# ARM_CTR_STM_DRV.net
KiCad netlist of a schematic drawn in Altium Designer
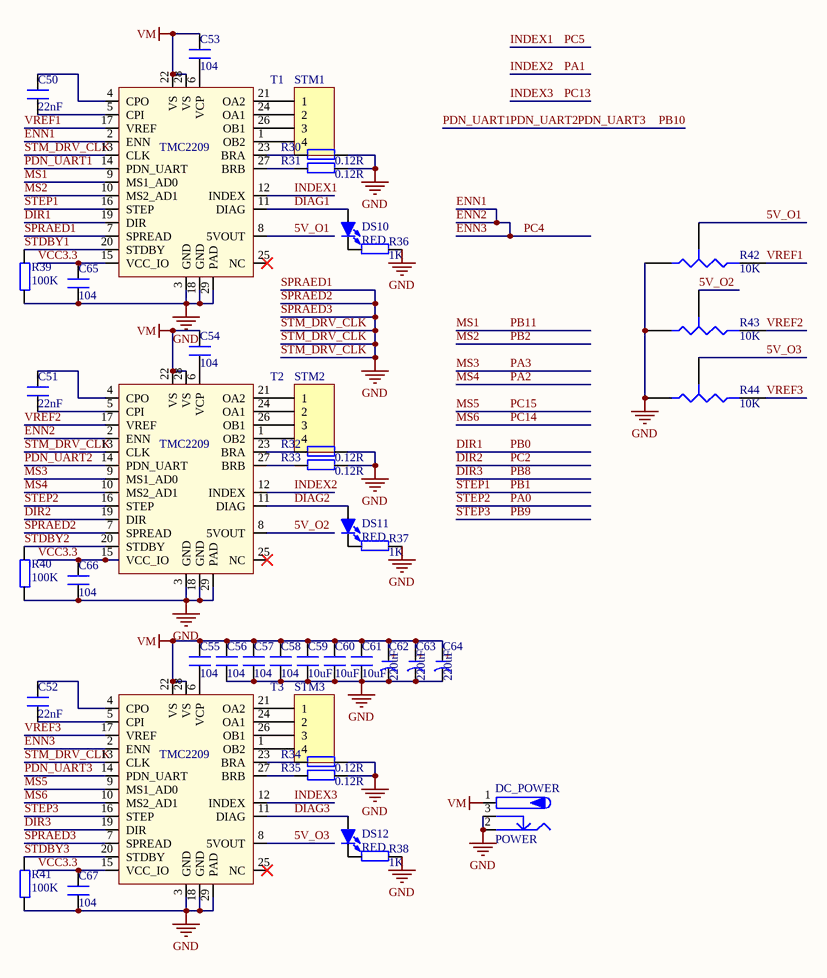
[diagram p0: ARM_CTR_STM_DRV.SchDoc]

(export (version "E")
  (design (tool "Eeschema 10.0.6"))
  (components
    (comp (ref "C50")
      (value "22nF")
      (footprint "C 0603_L")
      (libsource (lib "WarShip V3 STM32103封装库") (part "C"))
    )
    (comp (ref "C51")
      (value "22nF")
      (footprint "C 0603_L")
      (libsource (lib "WarShip V3 STM32103封装库") (part "C"))
    )
    (comp (ref "C52")
      (value "22nF")
      (footprint "C 0603_L")
      (libsource (lib "WarShip V3 STM32103封装库") (part "C"))
    )
    (comp (ref "C53")
      (value "104")
      (footprint "C 0603_L")
      (libsource (lib "WarShip V3 STM32103封装库") (part "C"))
    )
    (comp (ref "C54")
      (value "104")
      (footprint "C 0603_L")
      (libsource (lib "WarShip V3 STM32103封装库") (part "C"))
    )
    (comp (ref "C55")
      (value "104")
      (footprint "C 0603_L")
      (libsource (lib "WarShip V3 STM32103封装库") (part "C"))
    )
    (comp (ref "C56")
      (value "104")
      (footprint "C 0603_L")
      (libsource (lib "WarShip V3 STM32103封装库") (part "C"))
    )
    (comp (ref "C57")
      (value "104")
      (footprint "C 0603_L")
      (libsource (lib "WarShip V3 STM32103封装库") (part "C"))
    )
    (comp (ref "C58")
      (value "104")
      (footprint "C 0603_L")
      (libsource (lib "WarShip V3 STM32103封装库") (part "C"))
    )
    (comp (ref "C59")
      (value "10uF")
      (footprint "C 0603_L")
      (libsource (lib "WarShip V3 STM32103封装库") (part "C"))
    )
    (comp (ref "C60")
      (value "10uF")
      (footprint "C 0603_L")
      (libsource (lib "WarShip V3 STM32103封装库") (part "C"))
    )
    (comp (ref "C61")
      (value "10uF")
      (footprint "C 0603_L")
      (libsource (lib "WarShip V3 STM32103封装库") (part "C"))
    )
    (comp (ref "C62")
      (value "220uF")
      (footprint "CM D(6.3*5.4)")
      (description "贴片电解电容")
      (fields (field (name "版权归属") "源创客"))
      (libsource (lib "IMX6UL_ALPHA(底板)_V2.0") (part "C-CM"))
    )
    (comp (ref "C63")
      (value "220uF")
      (footprint "CM D(6.3*5.4)")
      (description "贴片电解电容")
      (fields (field (name "版权归属") "源创客"))
      (libsource (lib "IMX6UL_ALPHA(底板)_V2.0") (part "C-CM"))
    )
    (comp (ref "C64")
      (value "220uF")
      (footprint "CM D(6.3*5.4)")
      (description "贴片电解电容")
      (fields (field (name "版权归属") "源创客"))
      (libsource (lib "IMX6UL_ALPHA(底板)_V2.0") (part "C-CM"))
    )
    (comp (ref "C65")
      (value "104")
      (footprint "C 0603_L")
      (libsource (lib "WarShip V3 STM32103封装库") (part "C"))
    )
    (comp (ref "C66")
      (value "104")
      (footprint "C 0603_L")
      (libsource (lib "WarShip V3 STM32103封装库") (part "C"))
    )
    (comp (ref "C67")
      (value "104")
      (footprint "C 0603_L")
      (libsource (lib "WarShip V3 STM32103封装库") (part "C"))
    )
    (comp (ref "DC_POWER")
      (value "POWER")
      (footprint "DC10B")
      (description "低压电源接口")
      (fields (field (name "版权归属") "源创客"))
      (libsource (lib "IMX6UL_ALPHA(底板)_V2.0") (part "P-DC"))
    )
    (comp (ref "DS10")
      (value "RED")
      (footprint "LED 0805R")
      (description "贴片LED")
      (fields (field (name "版权归属") "源创客"))
      (libsource (lib "IMX6UL_ALPHA(底板)_V2.0") (part "LED-SMD"))
    )
    (comp (ref "DS11")
      (value "RED")
      (footprint "LED 0805R")
      (description "贴片LED")
      (fields (field (name "版权归属") "源创客"))
      (libsource (lib "IMX6UL_ALPHA(底板)_V2.0") (part "LED-SMD"))
    )
    (comp (ref "DS12")
      (value "RED")
      (footprint "LED 0805R")
      (description "贴片LED")
      (fields (field (name "版权归属") "源创客"))
      (libsource (lib "IMX6UL_ALPHA(底板)_V2.0") (part "LED-SMD"))
    )
    (comp (ref "R30")
      (value "0.12R")
      (footprint "R 0805_L")
      (libsource (lib "WarShip V3 STM32103封装库") (part "R"))
    )
    (comp (ref "R31")
      (value "0.12R")
      (footprint "R 0805_L")
      (libsource (lib "WarShip V3 STM32103封装库") (part "R"))
    )
    (comp (ref "R32")
      (value "0.12R")
      (footprint "R 0805_L")
      (libsource (lib "WarShip V3 STM32103封装库") (part "R"))
    )
    (comp (ref "R33")
      (value "0.12R")
      (footprint "R 0805_L")
      (libsource (lib "WarShip V3 STM32103封装库") (part "R"))
    )
    (comp (ref "R34")
      (value "0.12R")
      (footprint "R 0805_L")
      (libsource (lib "WarShip V3 STM32103封装库") (part "R"))
    )
    (comp (ref "R35")
      (value "0.12R")
      (footprint "R 0805_L")
      (libsource (lib "WarShip V3 STM32103封装库") (part "R"))
    )
    (comp (ref "R36")
      (value "1K")
      (footprint "R 0603_L")
      (libsource (lib "WarShip V3 STM32103封装库") (part "R"))
    )
    (comp (ref "R37")
      (value "1K")
      (footprint "R 0603_L")
      (libsource (lib "WarShip V3 STM32103封装库") (part "R"))
    )
    (comp (ref "R38")
      (value "1K")
      (footprint "R 0603_L")
      (libsource (lib "WarShip V3 STM32103封装库") (part "R"))
    )
    (comp (ref "R39")
      (value "100K")
      (footprint "R 0603_L")
      (libsource (lib "WarShip V3 STM32103封装库") (part "R"))
    )
    (comp (ref "R40")
      (value "100K")
      (footprint "R 0603_L")
      (libsource (lib "WarShip V3 STM32103封装库") (part "R"))
    )
    (comp (ref "R41")
      (value "100K")
      (footprint "R 0603_L")
      (libsource (lib "WarShip V3 STM32103封装库") (part "R"))
    )
    (comp (ref "R42")
      (value "10K")
      (footprint "3362P")
      (description "Tapped Resistor")
      (fields (field (name "Comment") "Res Tap") (field (name "PUBLISHER") "Altium Limited"))
      (libsource (lib "Miscellaneous Devices") (part "Res Tap"))
    )
    (comp (ref "R43")
      (value "10K")
      (footprint "3362P")
      (description "Tapped Resistor")
      (fields (field (name "Comment") "Res Tap") (field (name "PUBLISHER") "Altium Limited"))
      (libsource (lib "Miscellaneous Devices") (part "Res Tap"))
    )
    (comp (ref "R44")
      (value "10K")
      (footprint "3362P")
      (description "Tapped Resistor")
      (fields (field (name "Comment") "Res Tap") (field (name "PUBLISHER") "Altium Limited"))
      (libsource (lib "Miscellaneous Devices") (part "Res Tap"))
    )
    (comp (ref "STM1")
      (value "Header 4")
      (footprint "XH2.54-WI-4P")
      (description "Header, 4-Pin")
      (fields (field (name "PUBLISHER") "Altium Limited"))
      (libsource (lib "Miscellaneous Connectors") (part "Header 4"))
    )
    (comp (ref "STM2")
      (value "Header 4")
      (footprint "XH2.54-WI-4P")
      (description "Header, 4-Pin")
      (fields (field (name "PUBLISHER") "Altium Limited"))
      (libsource (lib "Miscellaneous Connectors") (part "Header 4"))
    )
    (comp (ref "STM3")
      (value "Header 4")
      (footprint "XH2.54-WI-4P")
      (description "Header, 4-Pin")
      (fields (field (name "PUBLISHER") "Altium Limited"))
      (libsource (lib "Miscellaneous Connectors") (part "Header 4"))
    )
    (comp (ref "T1")
      (value "TMC2209")
      (footprint "QFN28 5x5_L")
      (description "步进电机驱动芯片")
      (libsource (lib "MINIBLDC") (part "TMC2209"))
    )
    (comp (ref "T2")
      (value "TMC2209")
      (footprint "QFN28 5x5_L")
      (description "步进电机驱动芯片")
      (libsource (lib "MINIBLDC") (part "TMC2209"))
    )
    (comp (ref "T3")
      (value "TMC2209")
      (footprint "QFN28 5x5_L")
      (description "步进电机驱动芯片")
      (libsource (lib "MINIBLDC") (part "TMC2209"))
    )
  )
  (nets
    (net (code "1") (name "/5V_O1") (class "Default")
      (node (ref "R42") (pin "3") (pinfunction "TAP_3") (pintype "passive"))
      (node (ref "T1") (pin "8") (pinfunction "5VOUT_8") (pintype "passive"))
    )
    (net (code "2") (name "/5V_O2") (class "Default")
      (node (ref "R43") (pin "3") (pinfunction "TAP_3") (pintype "passive"))
      (node (ref "T2") (pin "8") (pinfunction "5VOUT_8") (pintype "passive"))
    )
    (net (code "3") (name "/5V_O3") (class "Default")
      (node (ref "R44") (pin "3") (pinfunction "TAP_3") (pintype "passive"))
      (node (ref "T3") (pin "8") (pinfunction "5VOUT_8") (pintype "passive"))
    )
    (net (code "4") (name "/DIAG1") (class "Default")
      (node (ref "DS10") (pin "1") (pinfunction "A_1") (pintype "passive"))
      (node (ref "T1") (pin "11") (pinfunction "DIAG_11") (pintype "passive"))
    )
    (net (code "5") (name "/DIAG2") (class "Default")
      (node (ref "DS11") (pin "1") (pinfunction "A_1") (pintype "passive"))
      (node (ref "T2") (pin "11") (pinfunction "DIAG_11") (pintype "passive"))
    )
    (net (code "6") (name "/DIAG3") (class "Default")
      (node (ref "DS12") (pin "1") (pinfunction "A_1") (pintype "passive"))
      (node (ref "T3") (pin "11") (pinfunction "DIAG_11") (pintype "passive"))
    )
    (net (code "7") (name "/DIR1") (class "Default")
      (node (ref "T1") (pin "19") (pinfunction "DIR_19") (pintype "passive"))
    )
    (net (code "8") (name "/DIR2") (class "Default")
      (node (ref "T2") (pin "19") (pinfunction "DIR_19") (pintype "passive"))
    )
    (net (code "9") (name "/DIR3") (class "Default")
      (node (ref "T3") (pin "19") (pinfunction "DIR_19") (pintype "passive"))
    )
    (net (code "10") (name "/ENN1") (class "Default")
      (node (ref "T1") (pin "2") (pinfunction "ENN_2") (pintype "passive"))
      (node (ref "T2") (pin "2") (pinfunction "ENN_2") (pintype "passive"))
      (node (ref "T3") (pin "2") (pinfunction "ENN_2") (pintype "passive"))
    )
    (net (code "11") (name "/INDEX1") (class "Default")
      (node (ref "T1") (pin "12") (pinfunction "INDEX_12") (pintype "passive"))
    )
    (net (code "12") (name "/INDEX2") (class "Default")
      (node (ref "T2") (pin "12") (pinfunction "INDEX_12") (pintype "passive"))
    )
    (net (code "13") (name "/INDEX3") (class "Default")
      (node (ref "T3") (pin "12") (pinfunction "INDEX_12") (pintype "passive"))
    )
    (net (code "14") (name "/MS1") (class "Default")
      (node (ref "T1") (pin "9") (pinfunction "MS1_AD0_9") (pintype "passive"))
    )
    (net (code "15") (name "/MS2") (class "Default")
      (node (ref "T1") (pin "10") (pinfunction "MS2_AD1_10") (pintype "passive"))
    )
    (net (code "16") (name "/MS3") (class "Default")
      (node (ref "T2") (pin "9") (pinfunction "MS1_AD0_9") (pintype "passive"))
    )
    (net (code "17") (name "/MS4") (class "Default")
      (node (ref "T2") (pin "10") (pinfunction "MS2_AD1_10") (pintype "passive"))
    )
    (net (code "18") (name "/MS5") (class "Default")
      (node (ref "T3") (pin "9") (pinfunction "MS1_AD0_9") (pintype "passive"))
    )
    (net (code "19") (name "/MS6") (class "Default")
      (node (ref "T3") (pin "10") (pinfunction "MS2_AD1_10") (pintype "passive"))
    )
    (net (code "20") (name "/PA0") (class "Default")
      (node (ref "T2") (pin "16") (pinfunction "STEP_16") (pintype "passive"))
    )
    (net (code "21") (name "/PB1") (class "Default")
      (node (ref "T1") (pin "16") (pinfunction "STEP_16") (pintype "passive"))
    )
    (net (code "22") (name "/PB9") (class "Default")
      (node (ref "T3") (pin "16") (pinfunction "STEP_16") (pintype "passive"))
    )
    (net (code "23") (name "/PB10") (class "Default")
      (node (ref "T1") (pin "14") (pinfunction "PDN_UART_14") (pintype "passive"))
      (node (ref "T2") (pin "14") (pinfunction "PDN_UART_14") (pintype "passive"))
      (node (ref "T3") (pin "14") (pinfunction "PDN_UART_14") (pintype "passive"))
    )
    (net (code "24") (name "/STDBY1") (class "Default")
      (node (ref "R39") (pin "2") (pintype "passive"))
      (node (ref "T1") (pin "20") (pinfunction "STDBY_20") (pintype "passive"))
    )
    (net (code "25") (name "/STDBY2") (class "Default")
      (node (ref "R40") (pin "2") (pintype "passive"))
      (node (ref "T2") (pin "20") (pinfunction "STDBY_20") (pintype "passive"))
    )
    (net (code "26") (name "/STDBY3") (class "Default")
      (node (ref "R41") (pin "2") (pintype "passive"))
      (node (ref "T3") (pin "20") (pinfunction "STDBY_20") (pintype "passive"))
    )
    (net (code "27") (name "/VCC3.3") (class "Default")
      (node (ref "C65") (pin "2") (pintype "passive"))
      (node (ref "C66") (pin "2") (pintype "passive"))
      (node (ref "C67") (pin "2") (pintype "passive"))
      (node (ref "T1") (pin "15") (pinfunction "VCC_IO_15") (pintype "passive"))
      (node (ref "T2") (pin "15") (pinfunction "VCC_IO_15") (pintype "passive"))
      (node (ref "T3") (pin "15") (pinfunction "VCC_IO_15") (pintype "passive"))
    )
    (net (code "28") (name "/VREF1") (class "Default")
      (node (ref "R42") (pin "2") (pinfunction "B_2") (pintype "passive"))
      (node (ref "T1") (pin "17") (pinfunction "VREF_17") (pintype "passive"))
    )
    (net (code "29") (name "/VREF2") (class "Default")
      (node (ref "R43") (pin "2") (pinfunction "B_2") (pintype "passive"))
      (node (ref "T2") (pin "17") (pinfunction "VREF_17") (pintype "passive"))
    )
    (net (code "30") (name "/VREF3") (class "Default")
      (node (ref "R44") (pin "2") (pinfunction "B_2") (pintype "passive"))
      (node (ref "T3") (pin "17") (pinfunction "VREF_17") (pintype "passive"))
    )
    (net (code "31") (name "GND") (class "Default")
      (node (ref "C56") (pin "1") (pintype "passive"))
      (node (ref "C57") (pin "1") (pintype "passive"))
      (node (ref "C58") (pin "1") (pintype "passive"))
      (node (ref "C59") (pin "1") (pintype "passive"))
      (node (ref "C60") (pin "1") (pintype "passive"))
      (node (ref "C61") (pin "1") (pintype "passive"))
      (node (ref "C62") (pin "2") (pinfunction "K_2") (pintype "passive"))
      (node (ref "C63") (pin "2") (pinfunction "K_2") (pintype "passive"))
      (node (ref "C64") (pin "2") (pinfunction "K_2") (pintype "passive"))
      (node (ref "C65") (pin "1") (pintype "passive"))
      (node (ref "C66") (pin "1") (pintype "passive"))
      (node (ref "C67") (pin "1") (pintype "passive"))
      (node (ref "DC_POWER") (pin "2") (pintype "power_in"))
      (node (ref "DC_POWER") (pin "3") (pintype "power_in"))
      (node (ref "R30") (pin "1") (pintype "passive"))
      (node (ref "R31") (pin "1") (pintype "passive"))
      (node (ref "R32") (pin "1") (pintype "passive"))
      (node (ref "R33") (pin "1") (pintype "passive"))
      (node (ref "R34") (pin "1") (pintype "passive"))
      (node (ref "R35") (pin "1") (pintype "passive"))
      (node (ref "R36") (pin "1") (pintype "passive"))
      (node (ref "R37") (pin "1") (pintype "passive"))
      (node (ref "R38") (pin "1") (pintype "passive"))
      (node (ref "R39") (pin "1") (pintype "passive"))
      (node (ref "R40") (pin "1") (pintype "passive"))
      (node (ref "R41") (pin "1") (pintype "passive"))
      (node (ref "R42") (pin "1") (pinfunction "A_1") (pintype "passive"))
      (node (ref "R43") (pin "1") (pinfunction "A_1") (pintype "passive"))
      (node (ref "R44") (pin "1") (pinfunction "A_1") (pintype "passive"))
      (node (ref "T1") (pin "13") (pinfunction "CLK_13") (pintype "passive"))
      (node (ref "T1") (pin "18") (pinfunction "GND_18") (pintype "passive"))
      (node (ref "T1") (pin "29") (pinfunction "PAD_29") (pintype "passive"))
      (node (ref "T1") (pin "3") (pinfunction "GND_3") (pintype "passive"))
      (node (ref "T1") (pin "7") (pinfunction "SPREAD_7") (pintype "passive"))
      (node (ref "T2") (pin "13") (pinfunction "CLK_13") (pintype "passive"))
      (node (ref "T2") (pin "18") (pinfunction "GND_18") (pintype "passive"))
      (node (ref "T2") (pin "29") (pinfunction "PAD_29") (pintype "passive"))
      (node (ref "T2") (pin "3") (pinfunction "GND_3") (pintype "passive"))
      (node (ref "T2") (pin "7") (pinfunction "SPREAD_7") (pintype "passive"))
      (node (ref "T3") (pin "13") (pinfunction "CLK_13") (pintype "passive"))
      (node (ref "T3") (pin "18") (pinfunction "GND_18") (pintype "passive"))
      (node (ref "T3") (pin "29") (pinfunction "PAD_29") (pintype "passive"))
      (node (ref "T3") (pin "3") (pinfunction "GND_3") (pintype "passive"))
      (node (ref "T3") (pin "7") (pinfunction "SPREAD_7") (pintype "passive"))
    )
    (net (code "32") (name "Net-(DS10-K)") (class "Default")
      (node (ref "DS10") (pin "2") (pinfunction "K_2") (pintype "passive"))
      (node (ref "R36") (pin "2") (pintype "passive"))
    )
    (net (code "33") (name "Net-(DS11-K)") (class "Default")
      (node (ref "DS11") (pin "2") (pinfunction "K_2") (pintype "passive"))
      (node (ref "R37") (pin "2") (pintype "passive"))
    )
    (net (code "34") (name "Net-(DS12-K)") (class "Default")
      (node (ref "DS12") (pin "2") (pinfunction "K_2") (pintype "passive"))
      (node (ref "R38") (pin "2") (pintype "passive"))
    )
    (net (code "35") (name "Net-(T1-BRA)") (class "Default")
      (node (ref "R30") (pin "2") (pintype "passive"))
      (node (ref "T1") (pin "23") (pinfunction "BRA_23") (pintype "passive"))
    )
    (net (code "36") (name "Net-(T1-BRB)") (class "Default")
      (node (ref "R31") (pin "2") (pintype "passive"))
      (node (ref "T1") (pin "27") (pinfunction "BRB_27") (pintype "passive"))
    )
    (net (code "37") (name "Net-(T1-CPI)") (class "Default")
      (node (ref "C50") (pin "1") (pintype "passive"))
      (node (ref "T1") (pin "5") (pinfunction "CPI_5") (pintype "passive"))
    )
    (net (code "38") (name "Net-(T1-CPO)") (class "Default")
      (node (ref "C50") (pin "2") (pintype "passive"))
      (node (ref "T1") (pin "4") (pinfunction "CPO_4") (pintype "passive"))
    )
    (net (code "39") (name "Net-(T1-OA1)") (class "Default")
      (node (ref "STM1") (pin "2") (pinfunction "2_2") (pintype "passive"))
      (node (ref "T1") (pin "24") (pinfunction "OA1_24") (pintype "passive"))
    )
    (net (code "40") (name "Net-(T1-OA2)") (class "Default")
      (node (ref "STM1") (pin "1") (pinfunction "1_1") (pintype "passive"))
      (node (ref "T1") (pin "21") (pinfunction "OA2_21") (pintype "passive"))
    )
    (net (code "41") (name "Net-(T1-OB1)") (class "Default")
      (node (ref "STM1") (pin "3") (pinfunction "3_3") (pintype "passive"))
      (node (ref "T1") (pin "26") (pinfunction "OB1_26") (pintype "passive"))
    )
    (net (code "42") (name "Net-(T1-OB2)") (class "Default")
      (node (ref "STM1") (pin "4") (pinfunction "4_4") (pintype "passive"))
      (node (ref "T1") (pin "1") (pinfunction "OB2_1") (pintype "passive"))
    )
    (net (code "43") (name "Net-(T1-VCP)") (class "Default")
      (node (ref "C53") (pin "1") (pintype "passive"))
      (node (ref "T1") (pin "6") (pinfunction "VCP_6") (pintype "passive"))
    )
    (net (code "44") (name "Net-(T2-BRA)") (class "Default")
      (node (ref "R32") (pin "2") (pintype "passive"))
      (node (ref "T2") (pin "23") (pinfunction "BRA_23") (pintype "passive"))
    )
    (net (code "45") (name "Net-(T2-BRB)") (class "Default")
      (node (ref "R33") (pin "2") (pintype "passive"))
      (node (ref "T2") (pin "27") (pinfunction "BRB_27") (pintype "passive"))
    )
    (net (code "46") (name "Net-(T2-CPI)") (class "Default")
      (node (ref "C51") (pin "1") (pintype "passive"))
      (node (ref "T2") (pin "5") (pinfunction "CPI_5") (pintype "passive"))
    )
    (net (code "47") (name "Net-(T2-CPO)") (class "Default")
      (node (ref "C51") (pin "2") (pintype "passive"))
      (node (ref "T2") (pin "4") (pinfunction "CPO_4") (pintype "passive"))
    )
    (net (code "48") (name "Net-(T2-OA1)") (class "Default")
      (node (ref "STM2") (pin "2") (pinfunction "2_2") (pintype "passive"))
      (node (ref "T2") (pin "24") (pinfunction "OA1_24") (pintype "passive"))
    )
    (net (code "49") (name "Net-(T2-OA2)") (class "Default")
      (node (ref "STM2") (pin "1") (pinfunction "1_1") (pintype "passive"))
      (node (ref "T2") (pin "21") (pinfunction "OA2_21") (pintype "passive"))
    )
    (net (code "50") (name "Net-(T2-OB1)") (class "Default")
      (node (ref "STM2") (pin "3") (pinfunction "3_3") (pintype "passive"))
      (node (ref "T2") (pin "26") (pinfunction "OB1_26") (pintype "passive"))
    )
    (net (code "51") (name "Net-(T2-OB2)") (class "Default")
      (node (ref "STM2") (pin "4") (pinfunction "4_4") (pintype "passive"))
      (node (ref "T2") (pin "1") (pinfunction "OB2_1") (pintype "passive"))
    )
    (net (code "52") (name "Net-(T2-VCP)") (class "Default")
      (node (ref "C54") (pin "1") (pintype "passive"))
      (node (ref "T2") (pin "6") (pinfunction "VCP_6") (pintype "passive"))
    )
    (net (code "53") (name "Net-(T3-BRA)") (class "Default")
      (node (ref "R34") (pin "2") (pintype "passive"))
      (node (ref "T3") (pin "23") (pinfunction "BRA_23") (pintype "passive"))
    )
    (net (code "54") (name "Net-(T3-BRB)") (class "Default")
      (node (ref "R35") (pin "2") (pintype "passive"))
      (node (ref "T3") (pin "27") (pinfunction "BRB_27") (pintype "passive"))
    )
    (net (code "55") (name "Net-(T3-CPI)") (class "Default")
      (node (ref "C52") (pin "1") (pintype "passive"))
      (node (ref "T3") (pin "5") (pinfunction "CPI_5") (pintype "passive"))
    )
    (net (code "56") (name "Net-(T3-CPO)") (class "Default")
      (node (ref "C52") (pin "2") (pintype "passive"))
      (node (ref "T3") (pin "4") (pinfunction "CPO_4") (pintype "passive"))
    )
    (net (code "57") (name "Net-(T3-OA1)") (class "Default")
      (node (ref "STM3") (pin "2") (pinfunction "2_2") (pintype "passive"))
      (node (ref "T3") (pin "24") (pinfunction "OA1_24") (pintype "passive"))
    )
    (net (code "58") (name "Net-(T3-OA2)") (class "Default")
      (node (ref "STM3") (pin "1") (pinfunction "1_1") (pintype "passive"))
      (node (ref "T3") (pin "21") (pinfunction "OA2_21") (pintype "passive"))
    )
    (net (code "59") (name "Net-(T3-OB1)") (class "Default")
      (node (ref "STM3") (pin "3") (pinfunction "3_3") (pintype "passive"))
      (node (ref "T3") (pin "26") (pinfunction "OB1_26") (pintype "passive"))
    )
    (net (code "60") (name "Net-(T3-OB2)") (class "Default")
      (node (ref "STM3") (pin "4") (pinfunction "4_4") (pintype "passive"))
      (node (ref "T3") (pin "1") (pinfunction "OB2_1") (pintype "passive"))
    )
    (net (code "61") (name "Net-(T3-VCP)") (class "Default")
      (node (ref "C55") (pin "1") (pintype "passive"))
      (node (ref "T3") (pin "6") (pinfunction "VCP_6") (pintype "passive"))
    )
    (net (code "62") (name "VM") (class "Default")
      (node (ref "C53") (pin "2") (pintype "passive"))
      (node (ref "C54") (pin "2") (pintype "passive"))
      (node (ref "C55") (pin "2") (pintype "passive"))
      (node (ref "C56") (pin "2") (pintype "passive"))
      (node (ref "C57") (pin "2") (pintype "passive"))
      (node (ref "C58") (pin "2") (pintype "passive"))
      (node (ref "C59") (pin "2") (pintype "passive"))
      (node (ref "C60") (pin "2") (pintype "passive"))
      (node (ref "C61") (pin "2") (pintype "passive"))
      (node (ref "C62") (pin "1") (pinfunction "A_1") (pintype "passive"))
      (node (ref "C63") (pin "1") (pinfunction "A_1") (pintype "passive"))
      (node (ref "C64") (pin "1") (pinfunction "A_1") (pintype "passive"))
      (node (ref "DC_POWER") (pin "1") (pintype "power_in"))
      (node (ref "T1") (pin "22") (pinfunction "VS_22") (pintype "passive"))
      (node (ref "T1") (pin "28") (pinfunction "VS_28") (pintype "passive"))
      (node (ref "T2") (pin "22") (pinfunction "VS_22") (pintype "passive"))
      (node (ref "T2") (pin "28") (pinfunction "VS_28") (pintype "passive"))
      (node (ref "T3") (pin "22") (pinfunction "VS_22") (pintype "passive"))
      (node (ref "T3") (pin "28") (pinfunction "VS_28") (pintype "passive"))
    )
    (net (code "63") (name "unconnected-(T1-NC-Pad25)") (class "Default")
      (node (ref "T1") (pin "25") (pinfunction "NC_25") (pintype "passive+no_connect"))
    )
    (net (code "64") (name "unconnected-(T2-NC-Pad25)") (class "Default")
      (node (ref "T2") (pin "25") (pinfunction "NC_25") (pintype "passive+no_connect"))
    )
    (net (code "65") (name "unconnected-(T3-NC-Pad25)") (class "Default")
      (node (ref "T3") (pin "25") (pinfunction "NC_25") (pintype "passive+no_connect"))
    )
  )
)
